# SCH_Linefollower_2026-01-02.net
KiCad netlist of a schematic drawn in EasyEDA
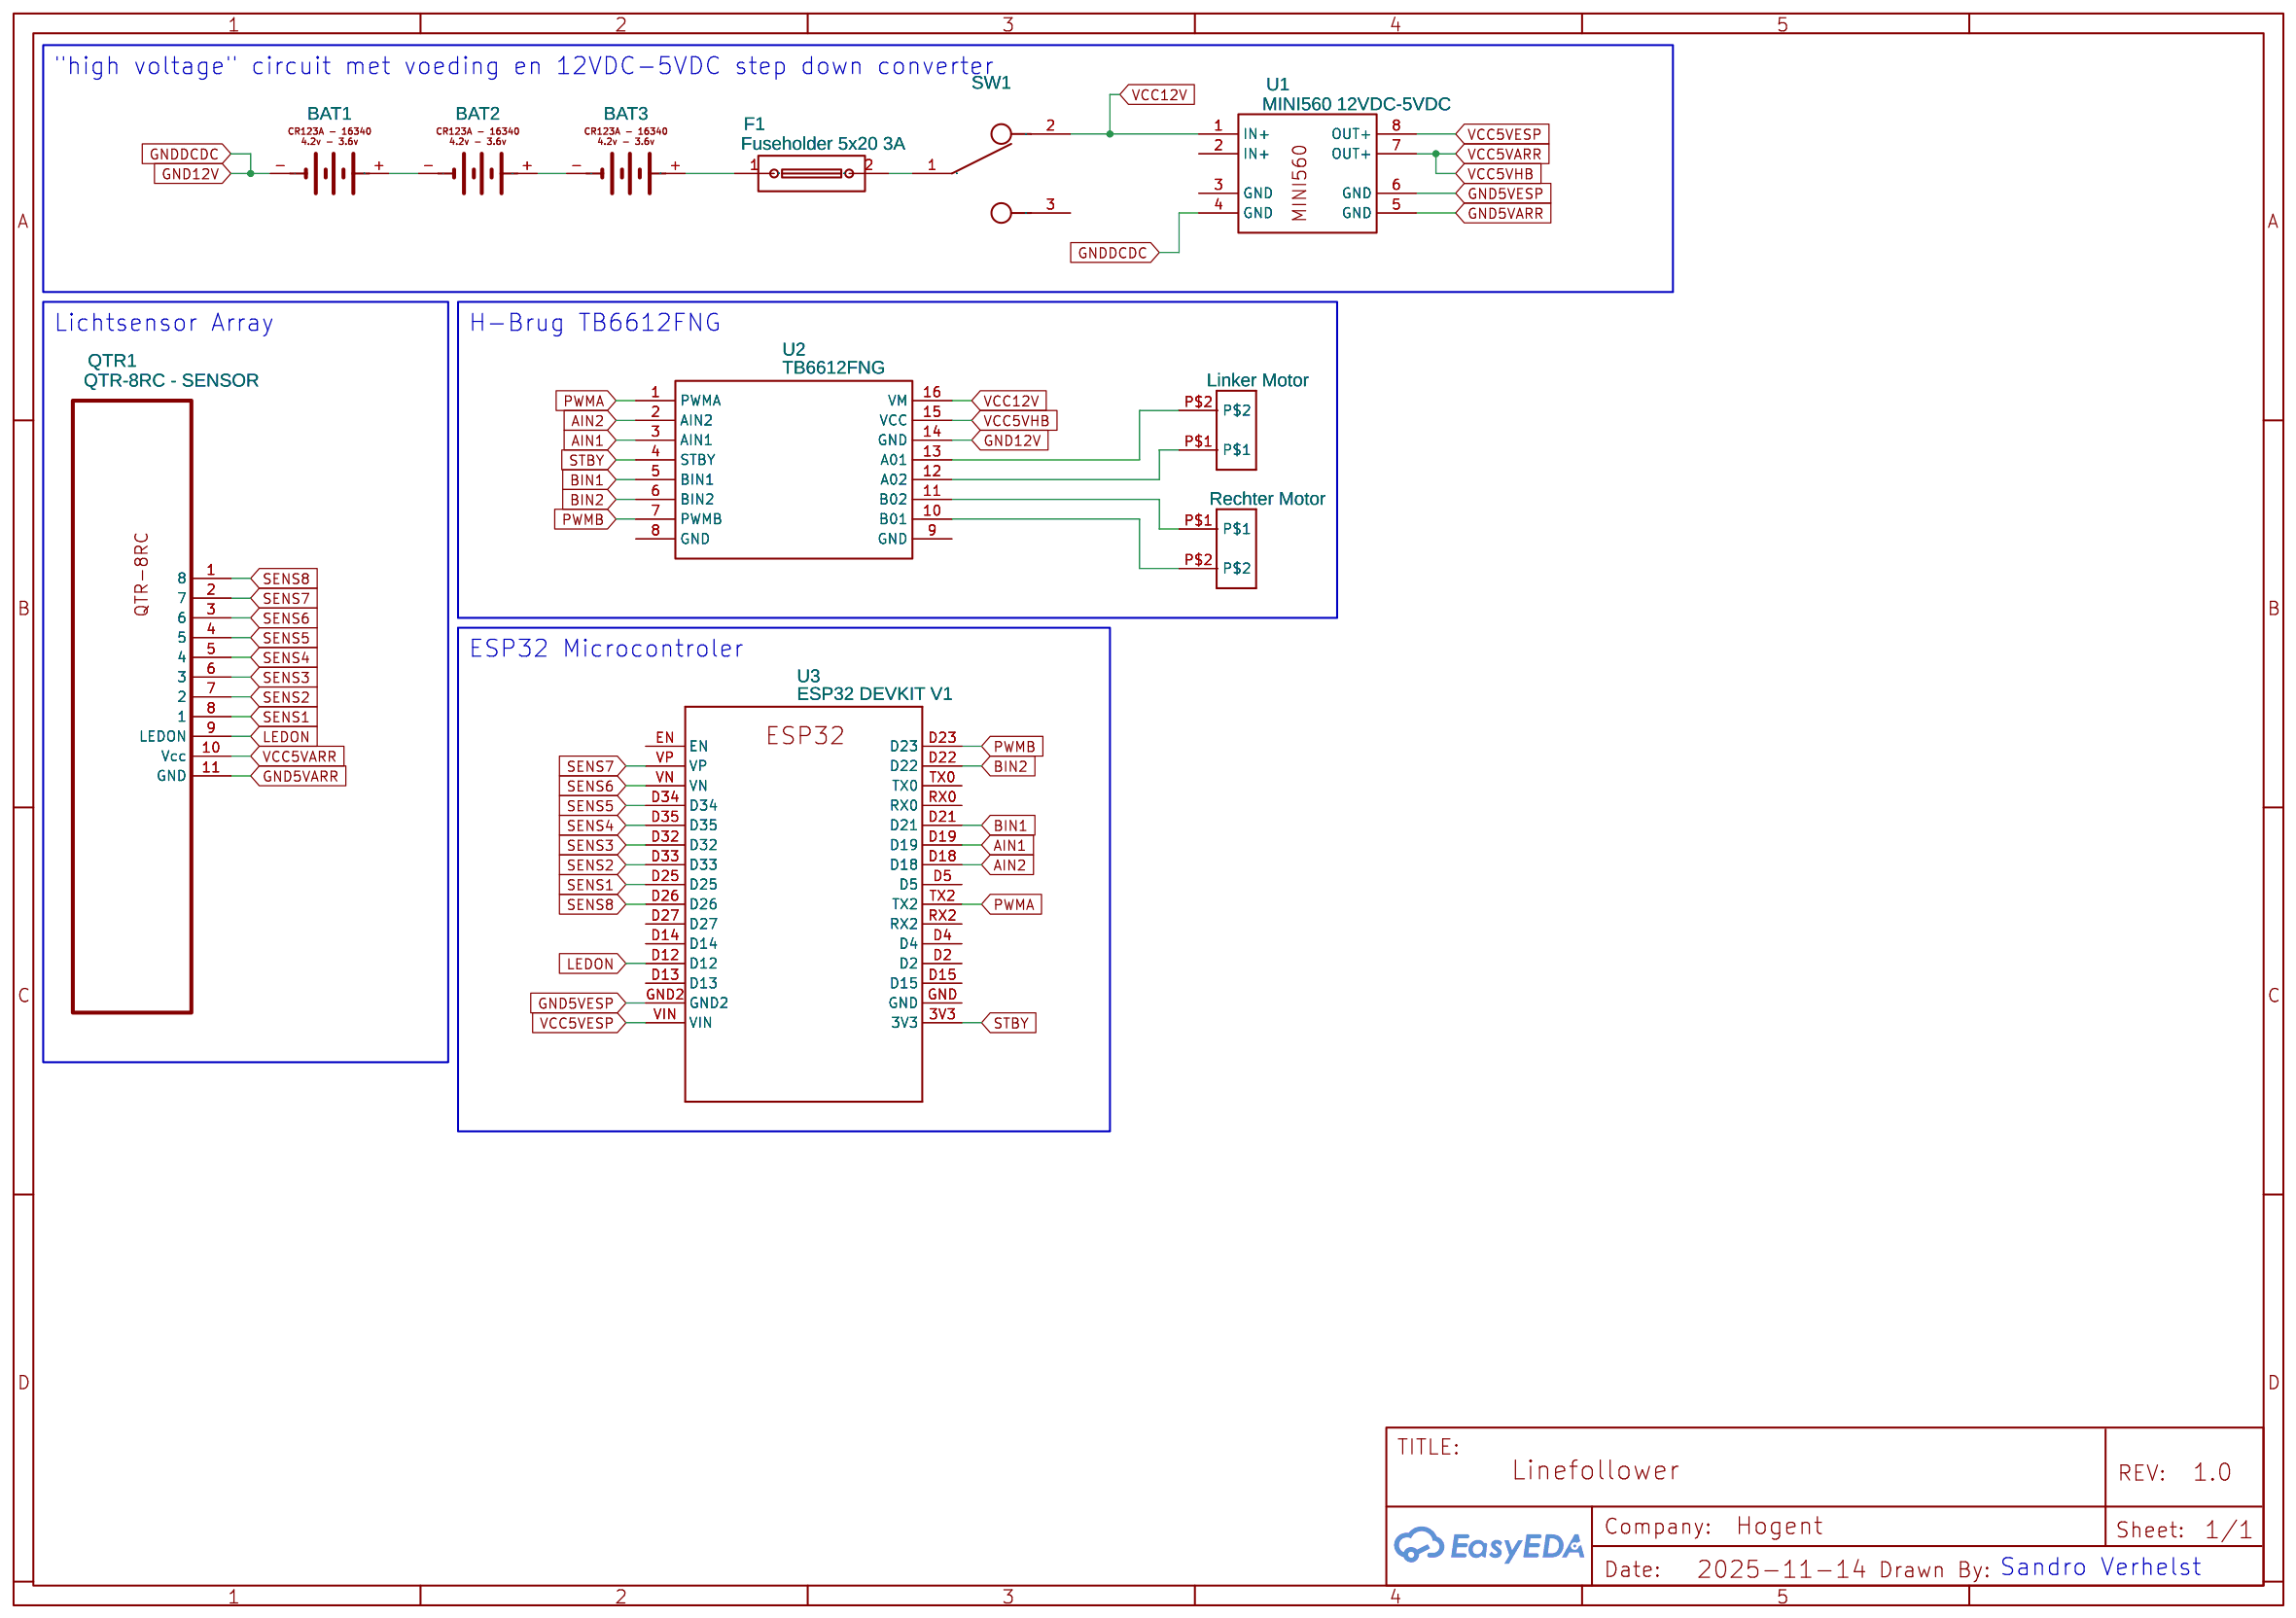
[diagram p0: schematic sheet]

(export (version "E")
  (design (tool "Eeschema 10.0.6"))
  (components
    (comp (ref "1") (value "Rechter Motor") (libsource (lib "") (part "2P_TERMINAL_BLOCK_PITCH_5MM")))
    (comp (ref "2") (value "Linker Motor") (libsource (lib "") (part "2P_TERMINAL_BLOCK_PITCH_5MM_1")))
    (comp (ref "BAT1") (value "BHC-CR123A meo") (libsource (lib "") (part "BHC-CR123A meo")))
    (comp (ref "BAT2") (value "BHC-CR123A meo") (libsource (lib "") (part "BHC-CR123A meo")))
    (comp (ref "BAT3") (value "BHC-CR123A meo") (libsource (lib "") (part "BHC-CR123A meo")))
    (comp (ref "F1")
      (value "Fuseholder 5x20 3A")
      (fields
        (field (name "Manufacturer Part") "5x20 BLX-Atype Fuse holder XC-7")
        (field (name "Manufacturer") "XCFuse")
      )
      (libsource (lib "") (part "Fuse_holder_5x20"))
    )
    (comp (ref "QTR1")
      (value "QTR-8RC - SENSOR")
      (fields (field (name "Manufacturer Part") "961") (field (name "Manufacturer") "Pololu"))
      (libsource (lib "") (part "QTR-8RC - SENSOR"))
    )
    (comp (ref "SW1")
      (value "SPDT_TOGGLE_SWITCH_4.7MM")
      (fields (field (name "Manufacturer Part") "CIT") (field (name "Manufacturer") "ANT11SF1CQE"))
      (libsource (lib "") (part "SPDT_TOGGLE_SWITCH_4.7MM"))
    )
    (comp (ref "U1") (value "MINI560 12VDC-5VDC") (libsource (lib "") (part "MINI560_DC-DC COPY")))
    (comp (ref "U2") (value "TB6612FNG") (libsource (lib "") (part "TB6612FNG")))
    (comp (ref "U3") (value "ESP32 DEVKIT V1") (libsource (lib "") (part "ESP32-DEVKIT-V1-30PIN")))
  )
  (nets
    (net (code "1") (name "AIN1") (class "Default")
      (node (ref "U2") (pin "3") (pinfunction "AIN1_3") (pintype "unspecified"))
      (node (ref "U3") (pin "D19") (pinfunction "D19_D19") (pintype "unspecified"))
    )
    (net (code "2") (name "AIN2") (class "Default")
      (node (ref "U2") (pin "2") (pinfunction "AIN2_2") (pintype "unspecified"))
      (node (ref "U3") (pin "D18") (pinfunction "D18_D18") (pintype "unspecified"))
    )
    (net (code "3") (name "BIN1") (class "Default")
      (node (ref "U2") (pin "5") (pinfunction "BIN1_5") (pintype "unspecified"))
      (node (ref "U3") (pin "D21") (pinfunction "D21_D21") (pintype "unspecified"))
    )
    (net (code "4") (name "BIN2") (class "Default")
      (node (ref "U2") (pin "6") (pinfunction "BIN2_6") (pintype "unspecified"))
      (node (ref "U3") (pin "D22") (pinfunction "D22_D22") (pintype "unspecified"))
    )
    (net (code "5") (name "GND5VARR") (class "Default")
      (node (ref "QTR1") (pin "11") (pinfunction "GND_11") (pintype "unspecified"))
      (node (ref "U1") (pin "5") (pinfunction "GND_5") (pintype "unspecified"))
    )
    (net (code "6") (name "GND5VESP") (class "Default")
      (node (ref "U1") (pin "6") (pinfunction "GND_6") (pintype "unspecified"))
      (node (ref "U3") (pin "GND2") (pinfunction "GND2_GND2") (pintype "unspecified"))
    )
    (net (code "7") (name "GND12V") (class "Default")
      (node (ref "BAT1") (pin "-") (pinfunction "-_-") (pintype "unspecified"))
      (node (ref "U1") (pin "4") (pinfunction "GND_4") (pintype "unspecified"))
      (node (ref "U2") (pin "14") (pinfunction "GND_14") (pintype "unspecified"))
    )
    (net (code "8") (name "LEDON") (class "Default")
      (node (ref "QTR1") (pin "9") (pinfunction "LEDON_9") (pintype "unspecified"))
      (node (ref "U3") (pin "D12") (pinfunction "D12_D12") (pintype "unspecified"))
    )
    (net (code "9") (name "Net-(BAT1-Pad+)") (class "Default")
      (node (ref "BAT1") (pin "+") (pinfunction "+_+") (pintype "unspecified"))
      (node (ref "BAT2") (pin "-") (pinfunction "-_-") (pintype "unspecified"))
    )
    (net (code "10") (name "Net-(BAT2-Pad+)") (class "Default")
      (node (ref "BAT2") (pin "+") (pinfunction "+_+") (pintype "unspecified"))
      (node (ref "BAT3") (pin "-") (pinfunction "-_-") (pintype "unspecified"))
    )
    (net (code "11") (name "Net-(BAT3-Pad+)") (class "Default")
      (node (ref "BAT3") (pin "+") (pinfunction "+_+") (pintype "unspecified"))
      (node (ref "F1") (pin "1") (pinfunction "1_1") (pintype "unspecified"))
    )
    (net (code "12") (name "Net-(F1-Pad2)") (class "Default")
      (node (ref "F1") (pin "2") (pinfunction "2_2") (pintype "unspecified"))
      (node (ref "SW1") (pin "1") (pinfunction "1_1") (pintype "unspecified"))
    )
    (net (code "13") (name "Net-(U2-A01)") (class "Default")
      (node (ref "2") (pin "P$2") (pinfunction "P$2_P$2") (pintype "bidirectional"))
      (node (ref "U2") (pin "13") (pinfunction "A01_13") (pintype "unspecified"))
    )
    (net (code "14") (name "Net-(U2-A02)") (class "Default")
      (node (ref "2") (pin "P$1") (pinfunction "P$1_P$1") (pintype "bidirectional"))
      (node (ref "U2") (pin "12") (pinfunction "A02_12") (pintype "unspecified"))
    )
    (net (code "15") (name "Net-(U2-B01)") (class "Default")
      (node (ref "1") (pin "P$2") (pinfunction "P$2_P$2") (pintype "bidirectional"))
      (node (ref "U2") (pin "10") (pinfunction "B01_10") (pintype "unspecified"))
    )
    (net (code "16") (name "Net-(U2-B02)") (class "Default")
      (node (ref "1") (pin "P$1") (pinfunction "P$1_P$1") (pintype "bidirectional"))
      (node (ref "U2") (pin "11") (pinfunction "B02_11") (pintype "unspecified"))
    )
    (net (code "17") (name "PWMA") (class "Default")
      (node (ref "U2") (pin "1") (pinfunction "PWMA_1") (pintype "unspecified"))
      (node (ref "U3") (pin "TX2") (pinfunction "TX2_TX2") (pintype "unspecified"))
    )
    (net (code "18") (name "PWMB") (class "Default")
      (node (ref "U2") (pin "7") (pinfunction "PWMB_7") (pintype "unspecified"))
      (node (ref "U3") (pin "D23") (pinfunction "D23_D23") (pintype "unspecified"))
    )
    (net (code "19") (name "SENS1") (class "Default")
      (node (ref "QTR1") (pin "8") (pinfunction "1_8") (pintype "unspecified"))
      (node (ref "U3") (pin "D25") (pinfunction "D25_D25") (pintype "unspecified"))
    )
    (net (code "20") (name "SENS2") (class "Default")
      (node (ref "QTR1") (pin "7") (pinfunction "2_7") (pintype "unspecified"))
      (node (ref "U3") (pin "D33") (pinfunction "D33_D33") (pintype "unspecified"))
    )
    (net (code "21") (name "SENS3") (class "Default")
      (node (ref "QTR1") (pin "6") (pinfunction "3_6") (pintype "unspecified"))
      (node (ref "U3") (pin "D32") (pinfunction "D32_D32") (pintype "unspecified"))
    )
    (net (code "22") (name "SENS4") (class "Default")
      (node (ref "QTR1") (pin "5") (pinfunction "4_5") (pintype "unspecified"))
      (node (ref "U3") (pin "D35") (pinfunction "D35_D35") (pintype "unspecified"))
    )
    (net (code "23") (name "SENS5") (class "Default")
      (node (ref "QTR1") (pin "4") (pinfunction "5_4") (pintype "unspecified"))
      (node (ref "U3") (pin "D34") (pinfunction "D34_D34") (pintype "unspecified"))
    )
    (net (code "24") (name "SENS6") (class "Default")
      (node (ref "QTR1") (pin "3") (pinfunction "6_3") (pintype "unspecified"))
      (node (ref "U3") (pin "VN") (pinfunction "VN_VN") (pintype "unspecified"))
    )
    (net (code "25") (name "SENS7") (class "Default")
      (node (ref "QTR1") (pin "2") (pinfunction "7_2") (pintype "unspecified"))
      (node (ref "U3") (pin "VP") (pinfunction "VP_VP") (pintype "unspecified"))
    )
    (net (code "26") (name "SENS8") (class "Default")
      (node (ref "QTR1") (pin "1") (pinfunction "8_1") (pintype "unspecified"))
      (node (ref "U3") (pin "D26") (pinfunction "D26_D26") (pintype "unspecified"))
    )
    (net (code "27") (name "STBY") (class "Default")
      (node (ref "U2") (pin "4") (pinfunction "STBY_4") (pintype "unspecified"))
      (node (ref "U3") (pin "3V3") (pinfunction "3V3_3V3") (pintype "unspecified"))
    )
    (net (code "28") (name "VCC5VARR") (class "Default")
      (node (ref "QTR1") (pin "10") (pinfunction "Vcc_10") (pintype "unspecified"))
      (node (ref "U1") (pin "7") (pinfunction "OUT+_7") (pintype "unspecified"))
      (node (ref "U2") (pin "15") (pinfunction "VCC_15") (pintype "unspecified"))
    )
    (net (code "29") (name "VCC5VESP") (class "Default")
      (node (ref "U1") (pin "8") (pinfunction "OUT+_8") (pintype "unspecified"))
      (node (ref "U3") (pin "VIN") (pinfunction "VIN_VIN") (pintype "unspecified"))
    )
    (net (code "30") (name "VCC12V") (class "Default")
      (node (ref "SW1") (pin "2") (pinfunction "2_2") (pintype "unspecified"))
      (node (ref "U1") (pin "1") (pinfunction "IN+_1") (pintype "unspecified"))
      (node (ref "U2") (pin "16") (pinfunction "VM_16") (pintype "unspecified"))
    )
    (net (code "31") (name "unconnected-(SW1-Pad3)") (class "Default")
      (node (ref "SW1") (pin "3") (pinfunction "3_3") (pintype "unspecified"))
    )
    (net (code "32") (name "unconnected-(U1-GND-Pad3)") (class "Default")
      (node (ref "U1") (pin "3") (pinfunction "GND_3") (pintype "unspecified"))
    )
    (net (code "33") (name "unconnected-(U1-IN+-Pad2)") (class "Default")
      (node (ref "U1") (pin "2") (pinfunction "IN+_2") (pintype "unspecified"))
    )
    (net (code "34") (name "unconnected-(U2-GND-Pad8)") (class "Default")
      (node (ref "U2") (pin "8") (pinfunction "GND_8") (pintype "unspecified"))
    )
    (net (code "35") (name "unconnected-(U2-GND-Pad9)") (class "Default")
      (node (ref "U2") (pin "9") (pinfunction "GND_9") (pintype "unspecified"))
    )
    (net (code "36") (name "unconnected-(U3-PadD2)") (class "Default")
      (node (ref "U3") (pin "D2") (pinfunction "D2_D2") (pintype "unspecified"))
    )
    (net (code "37") (name "unconnected-(U3-PadD4)") (class "Default")
      (node (ref "U3") (pin "D4") (pinfunction "D4_D4") (pintype "unspecified"))
    )
    (net (code "38") (name "unconnected-(U3-PadD5)") (class "Default")
      (node (ref "U3") (pin "D5") (pinfunction "D5_D5") (pintype "unspecified"))
    )
    (net (code "39") (name "unconnected-(U3-PadD13)") (class "Default")
      (node (ref "U3") (pin "D13") (pinfunction "D13_D13") (pintype "unspecified"))
    )
    (net (code "40") (name "unconnected-(U3-PadD14)") (class "Default")
      (node (ref "U3") (pin "D14") (pinfunction "D14_D14") (pintype "unspecified"))
    )
    (net (code "41") (name "unconnected-(U3-PadD15)") (class "Default")
      (node (ref "U3") (pin "D15") (pinfunction "D15_D15") (pintype "unspecified"))
    )
    (net (code "42") (name "unconnected-(U3-PadD27)") (class "Default")
      (node (ref "U3") (pin "D27") (pinfunction "D27_D27") (pintype "unspecified"))
    )
    (net (code "43") (name "unconnected-(U3-PadEN)") (class "Default")
      (node (ref "U3") (pin "EN") (pinfunction "EN_EN") (pintype "unspecified"))
    )
    (net (code "44") (name "unconnected-(U3-PadGND)") (class "Default")
      (node (ref "U3") (pin "GND") (pinfunction "GND_GND") (pintype "unspecified"))
    )
    (net (code "45") (name "unconnected-(U3-PadRX0)") (class "Default")
      (node (ref "U3") (pin "RX0") (pinfunction "RX0_RX0") (pintype "unspecified"))
    )
    (net (code "46") (name "unconnected-(U3-PadRX2)") (class "Default")
      (node (ref "U3") (pin "RX2") (pinfunction "RX2_RX2") (pintype "unspecified"))
    )
    (net (code "47") (name "unconnected-(U3-PadTX0)") (class "Default")
      (node (ref "U3") (pin "TX0") (pinfunction "TX0_TX0") (pintype "unspecified"))
    )
  )
)
